# BBB_CNC_V3.net
KiCad netlist of a schematic drawn in EAGLE
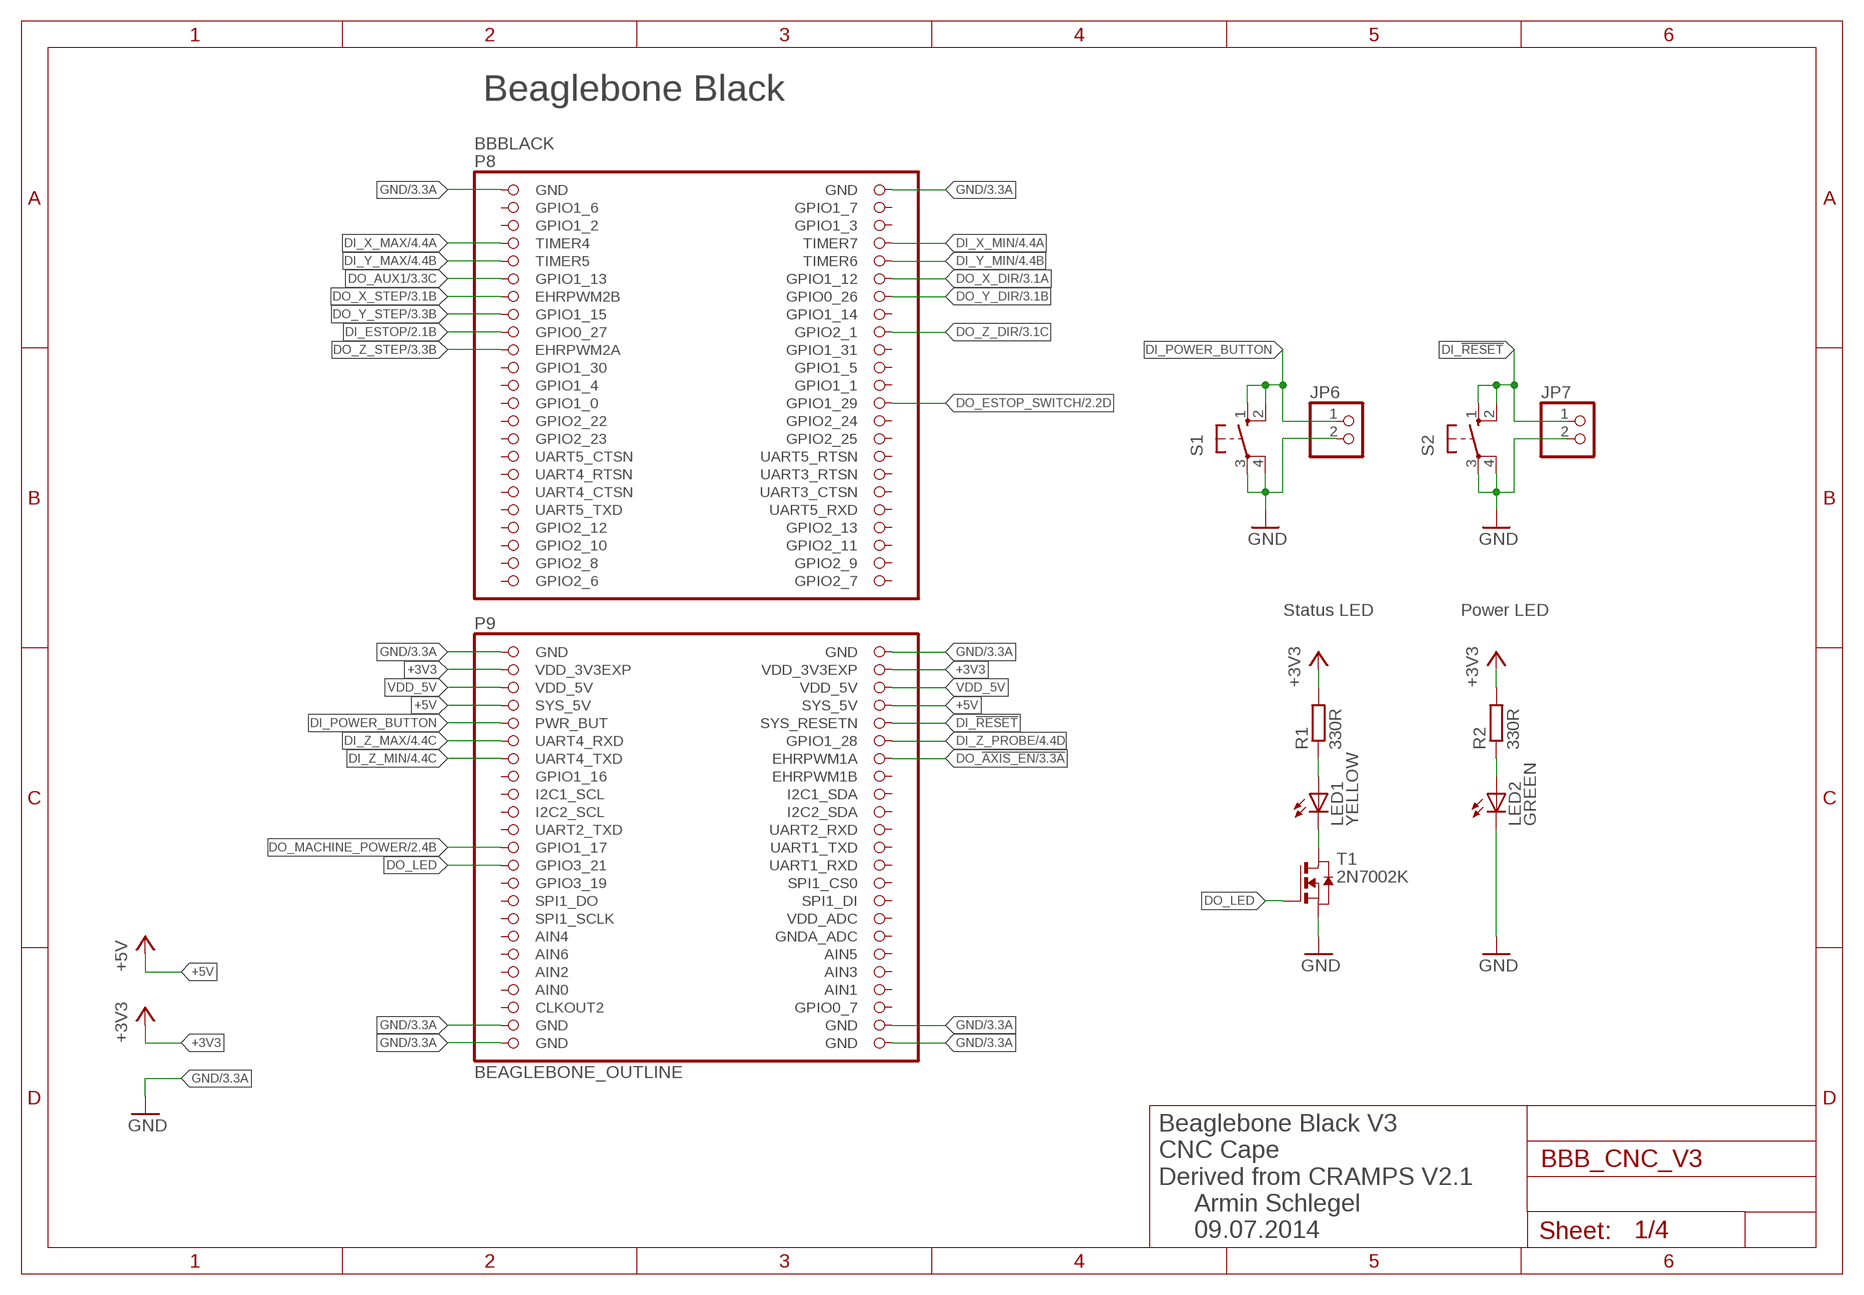
[diagram p0: schematic, sheet 1]
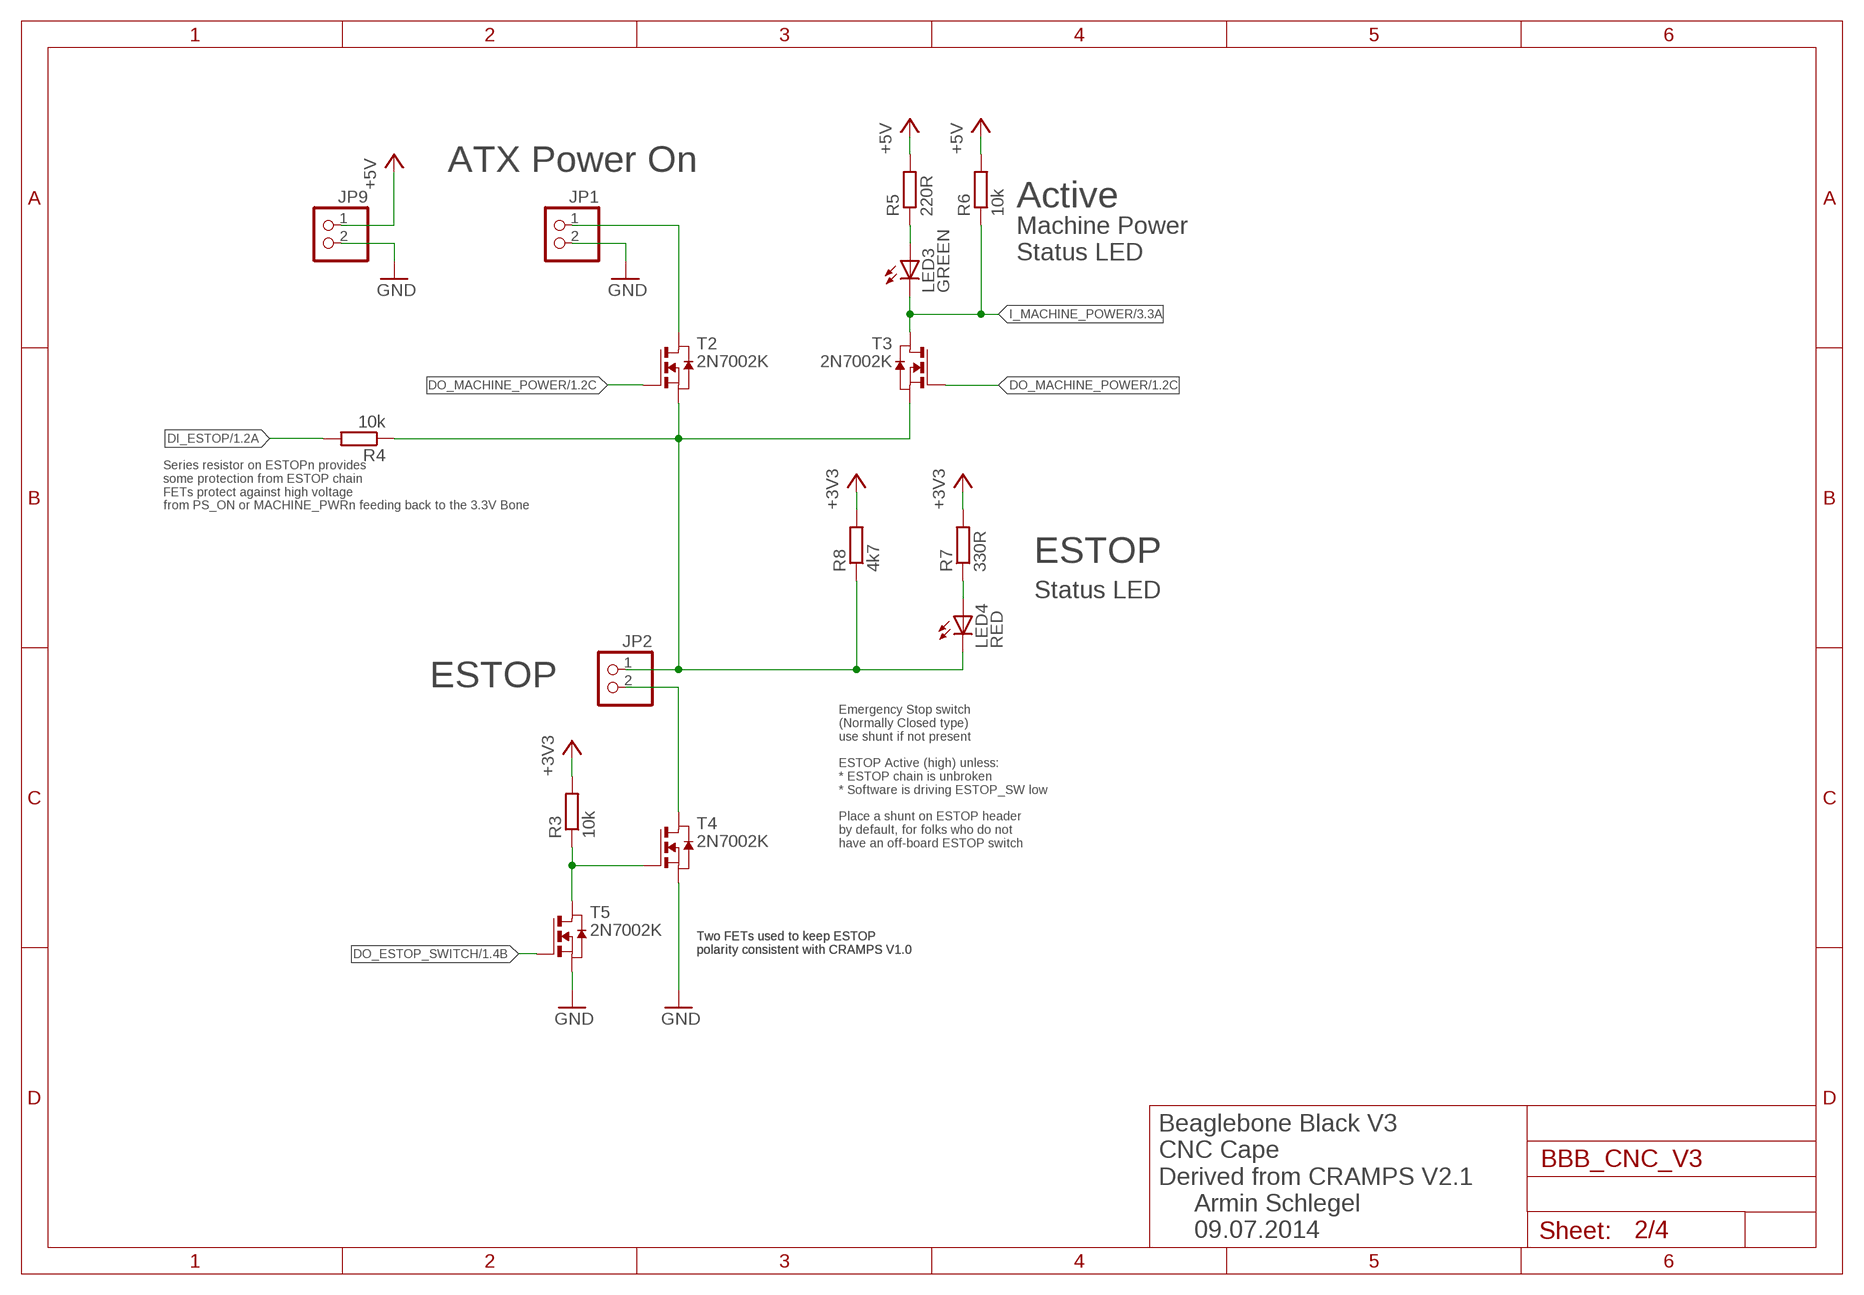
[diagram p1: schematic, sheet 2]
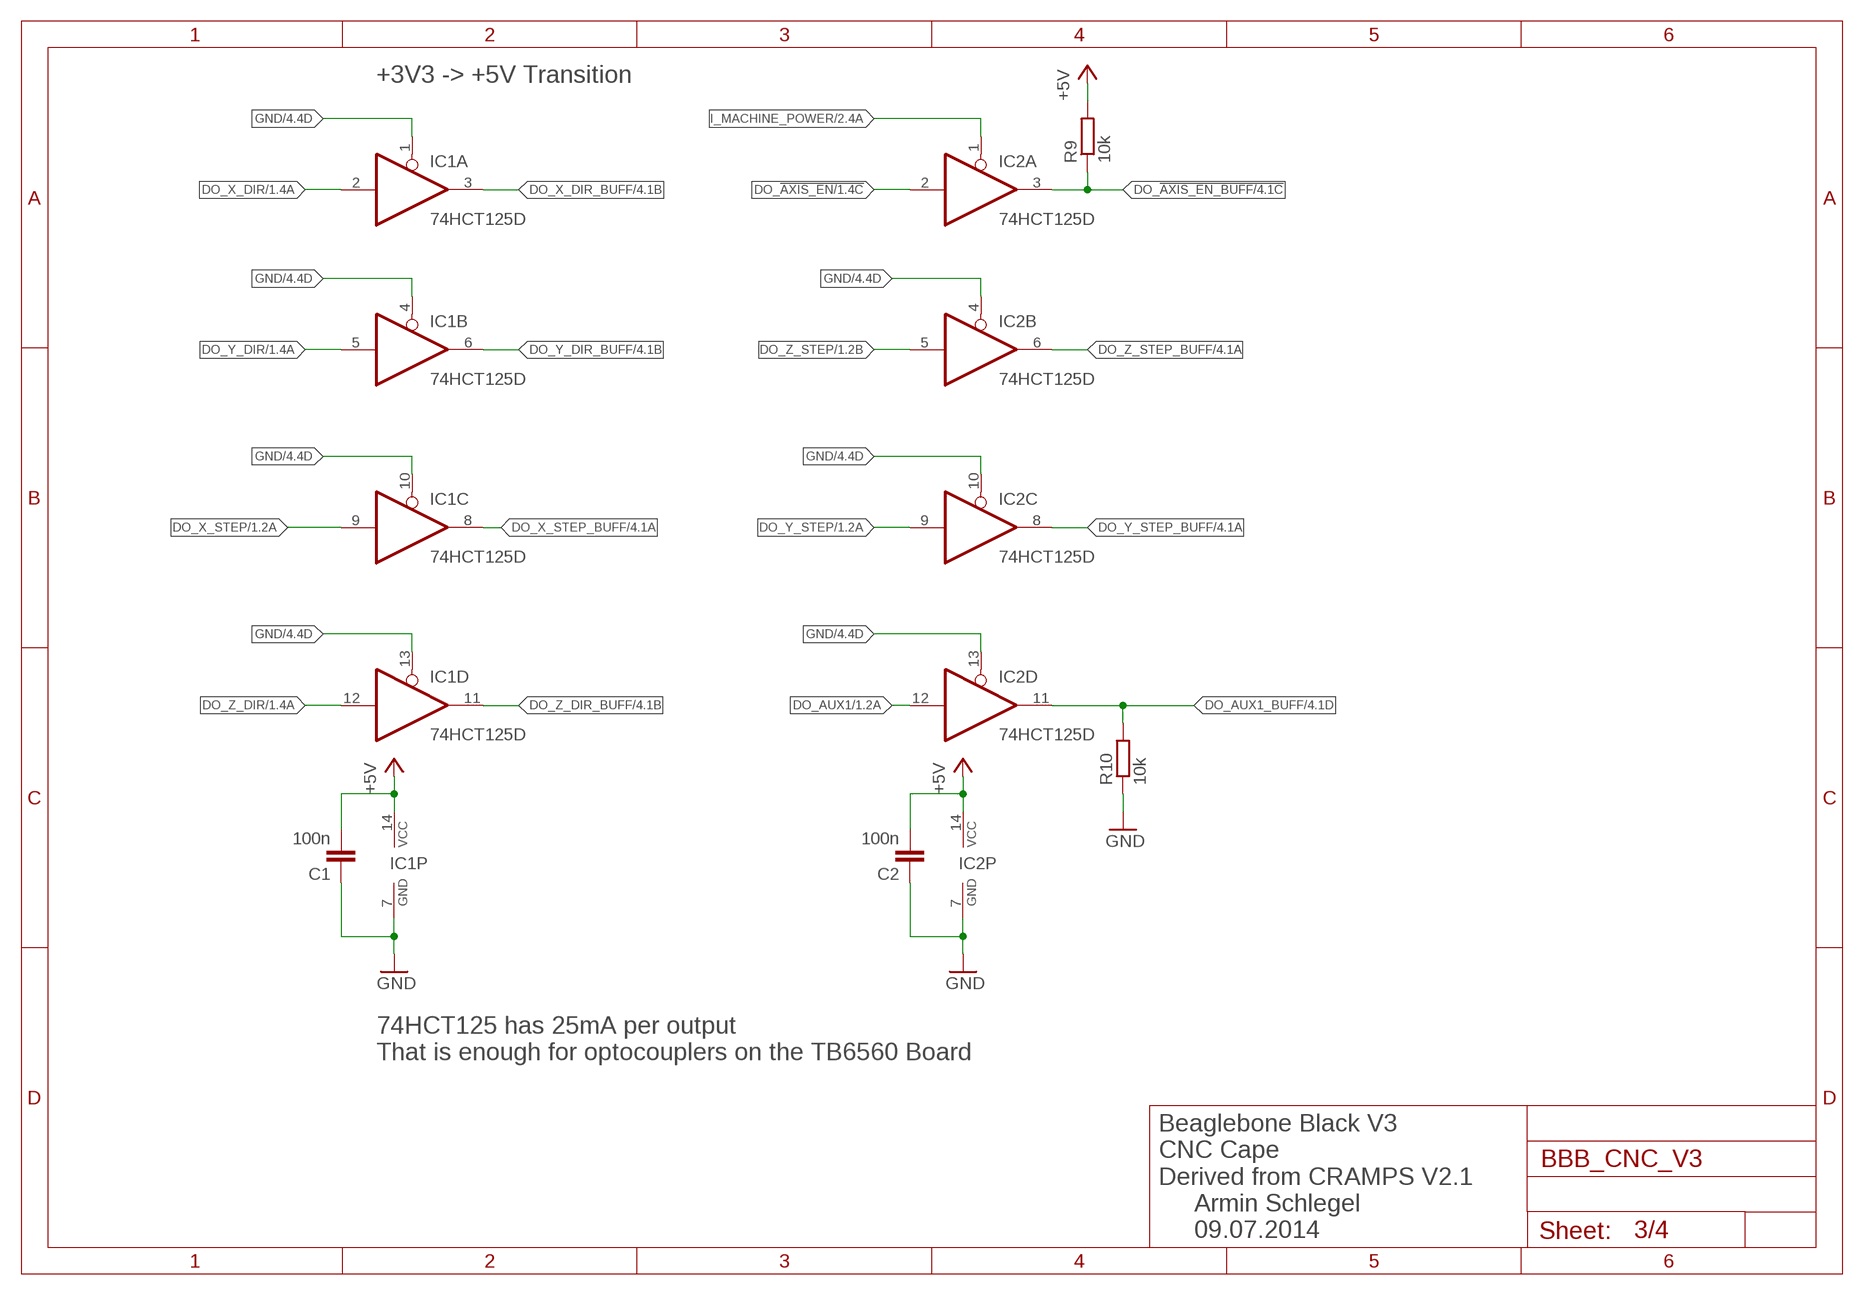
[diagram p2: schematic, sheet 3]
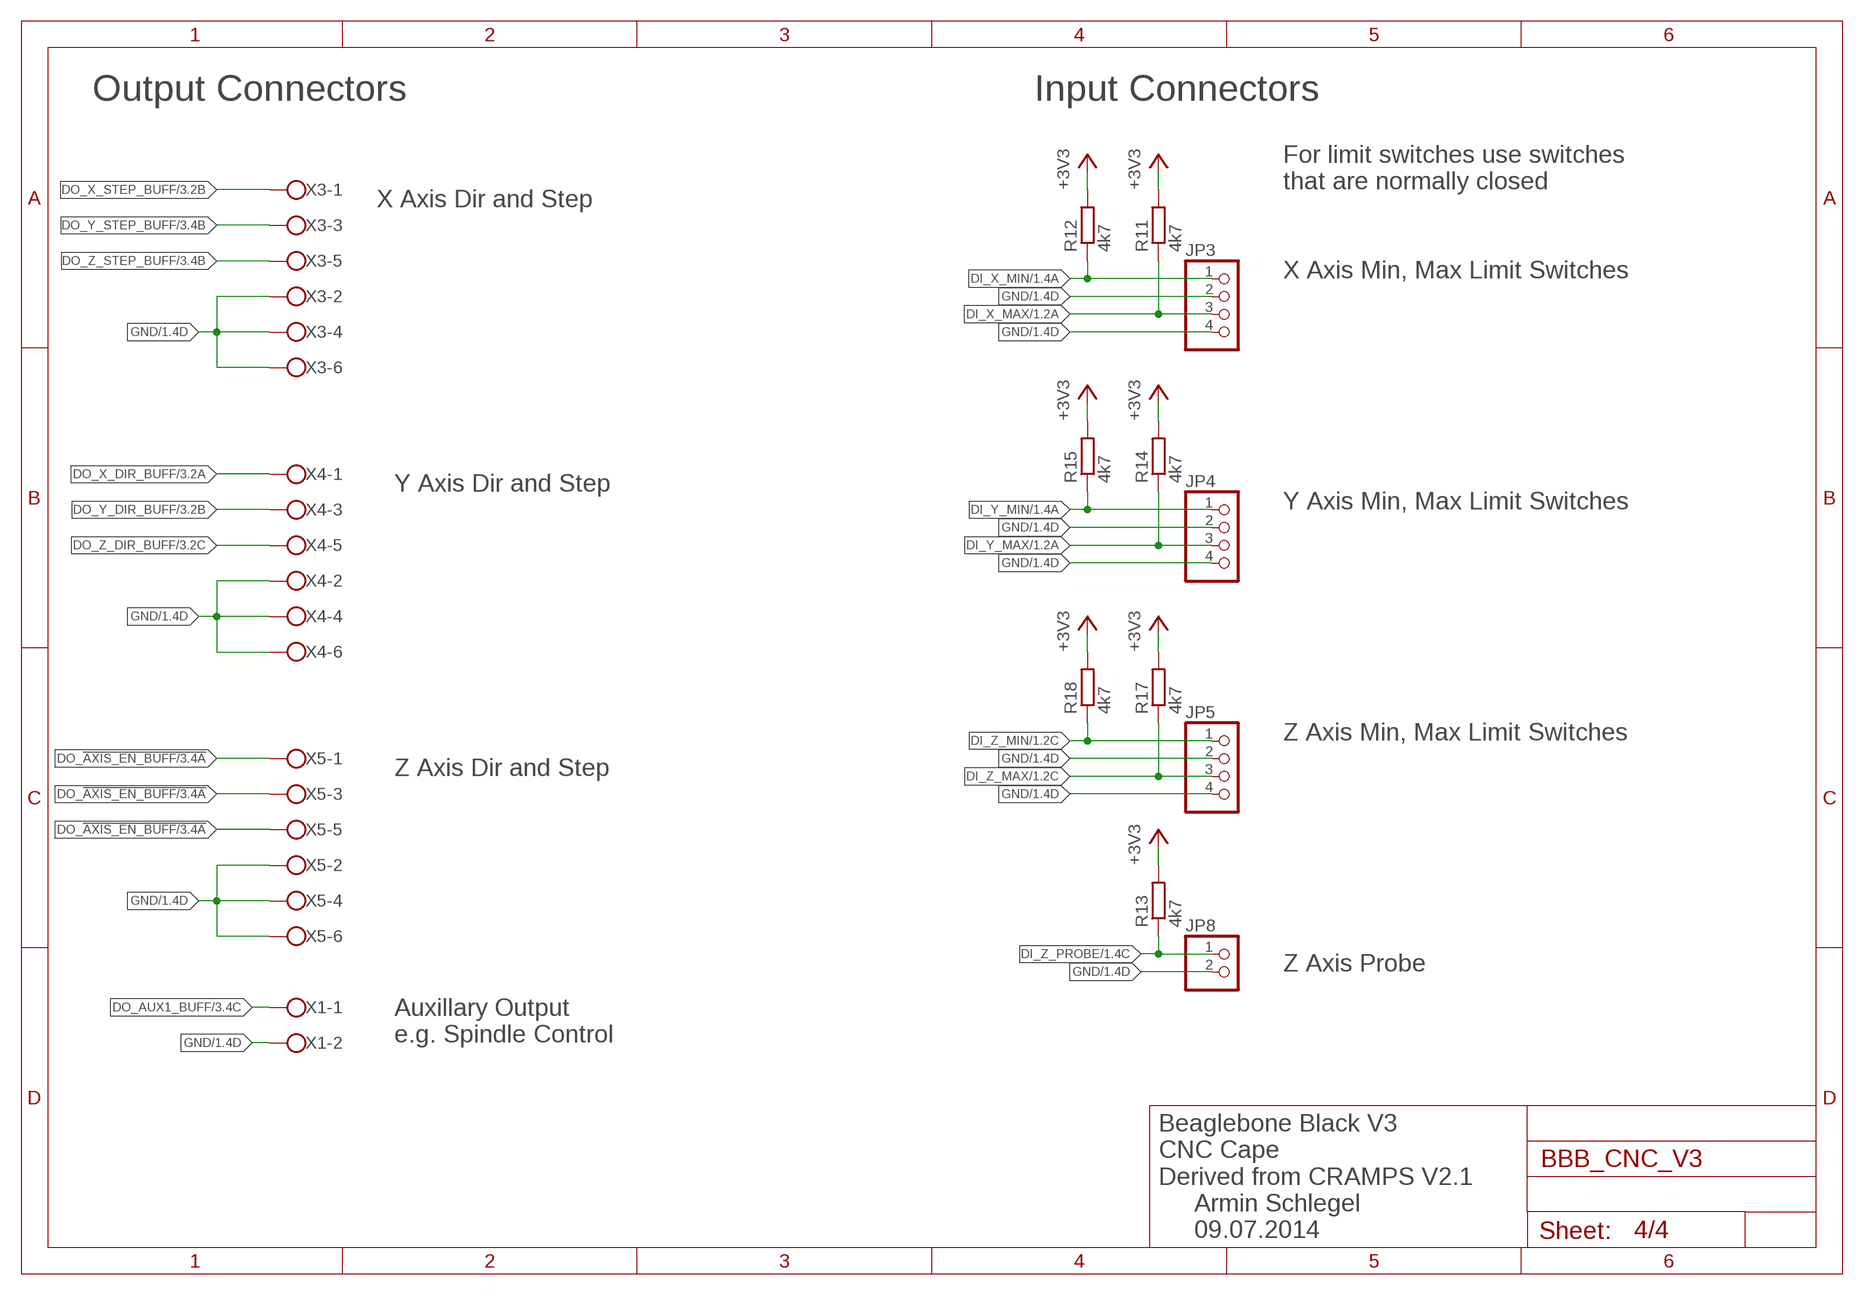
[diagram p3: schematic, sheet 4]

(export (version "E")
  (design (tool "Eeschema 10.0.6"))
  (components
    (comp (ref "BBBLACK")
      (value "BEAGLEBONE_OUTLINE")
      (footprint "eagle-import:BEAGLEBONE_SHIELD")
      (libsource (lib "eagle-import") (part "BEAGLEBONE_OUTLINE"))
    )
    (comp (ref "JP6")
      (value "PINHD-1X2")
      (footprint "eagle-import:1X02")
      (libsource (lib "eagle-import") (part "PINHD-1X2"))
    )
    (comp (ref "JP7")
      (value "PINHD-1X2")
      (footprint "eagle-import:1X02")
      (libsource (lib "eagle-import") (part "PINHD-1X2"))
    )
    (comp (ref "LED1")
      (value "YELLOW")
      (footprint "eagle-import:SML0805")
      (libsource (lib "eagle-import") (part "LEDSML0805"))
    )
    (comp (ref "LED2")
      (value "GREEN")
      (footprint "eagle-import:SML0805")
      (libsource (lib "eagle-import") (part "LEDSML0805"))
    )
    (comp (ref "R1")
      (value "330R")
      (footprint "eagle-import:R0603")
      (libsource (lib "eagle-import") (part "R-EU_R0603"))
    )
    (comp (ref "R2")
      (value "330R")
      (footprint "eagle-import:R0603")
      (libsource (lib "eagle-import") (part "R-EU_R0603"))
    )
    (comp (ref "S1")
      (value "10-XX")
      (footprint "eagle-import:B3F-10XX")
      (fields (field (name "MPN") "B3F-1000"))
      (libsource (lib "eagle-import") (part "10-XX"))
    )
    (comp (ref "S2")
      (value "10-XX")
      (footprint "eagle-import:B3F-10XX")
      (fields (field (name "MPN") "B3F-1000"))
      (libsource (lib "eagle-import") (part "10-XX"))
    )
    (comp (ref "T1")
      (value "2N7002K")
      (footprint "eagle-import:SOT-23")
      (libsource (lib "eagle-import") (part "NMOSSOT23"))
    )
    (comp (ref "JP1")
      (value "PINHD-1X2")
      (footprint "eagle-import:1X02")
      (libsource (lib "eagle-import") (part "PINHD-1X2"))
    )
    (comp (ref "JP2")
      (value "PINHD-1X2")
      (footprint "eagle-import:1X02")
      (libsource (lib "eagle-import") (part "PINHD-1X2"))
    )
    (comp (ref "JP9")
      (value "PINHD-1X2")
      (footprint "eagle-import:1X02")
      (libsource (lib "eagle-import") (part "PINHD-1X2"))
    )
    (comp (ref "LED3")
      (value "GREEN")
      (footprint "eagle-import:SML0805")
      (libsource (lib "eagle-import") (part "LEDSML0805"))
    )
    (comp (ref "LED4")
      (value "RED")
      (footprint "eagle-import:SML0805")
      (libsource (lib "eagle-import") (part "LEDSML0805"))
    )
    (comp (ref "R3")
      (value "10k")
      (footprint "eagle-import:R0603")
      (libsource (lib "eagle-import") (part "R-EU_R0603"))
    )
    (comp (ref "R4")
      (value "10k")
      (footprint "eagle-import:R0603")
      (libsource (lib "eagle-import") (part "R-EU_R0603"))
    )
    (comp (ref "R5")
      (value "220R")
      (footprint "eagle-import:R0603")
      (libsource (lib "eagle-import") (part "R-EU_R0603"))
    )
    (comp (ref "R6")
      (value "10k")
      (footprint "eagle-import:R0603")
      (libsource (lib "eagle-import") (part "R-EU_R0603"))
    )
    (comp (ref "R7")
      (value "330R")
      (footprint "eagle-import:R0603")
      (libsource (lib "eagle-import") (part "R-EU_R0603"))
    )
    (comp (ref "R8")
      (value "4k7")
      (footprint "eagle-import:R0603")
      (libsource (lib "eagle-import") (part "R-EU_R0603"))
    )
    (comp (ref "T2")
      (value "2N7002K")
      (footprint "eagle-import:SOT-23")
      (libsource (lib "eagle-import") (part "NMOSSOT23"))
    )
    (comp (ref "T3")
      (value "2N7002K")
      (footprint "eagle-import:SOT-23")
      (libsource (lib "eagle-import") (part "NMOSSOT23"))
    )
    (comp (ref "T4")
      (value "2N7002K")
      (footprint "eagle-import:SOT-23")
      (libsource (lib "eagle-import") (part "NMOSSOT23"))
    )
    (comp (ref "T5")
      (value "2N7002K")
      (footprint "eagle-import:SOT-23")
      (libsource (lib "eagle-import") (part "NMOSSOT23"))
    )
    (comp (ref "C1")
      (value "100n")
      (footprint "eagle-import:C0603K")
      (libsource (lib "eagle-import") (part "C-EUC0603K"))
    )
    (comp (ref "C2")
      (value "100n")
      (footprint "eagle-import:C0603K")
      (libsource (lib "eagle-import") (part "C-EUC0603K"))
    )
    (comp (ref "IC1")
      (value "74HCT125D")
      (footprint "eagle-import:SO14")
      (libsource (lib "eagle-import") (part "74125DHCT"))
    )
    (comp (ref "IC2")
      (value "74HCT125D")
      (footprint "eagle-import:SO14")
      (libsource (lib "eagle-import") (part "74125DHCT"))
    )
    (comp (ref "R9")
      (value "10k")
      (footprint "eagle-import:R0603")
      (libsource (lib "eagle-import") (part "R-EU_R0603"))
    )
    (comp (ref "R10")
      (value "10k")
      (footprint "eagle-import:R0603")
      (libsource (lib "eagle-import") (part "R-EU_R0603"))
    )
    (comp (ref "JP3")
      (value "PINHD-1X4")
      (footprint "eagle-import:1X04")
      (libsource (lib "eagle-import") (part "PINHD-1X4"))
    )
    (comp (ref "JP4")
      (value "PINHD-1X4")
      (footprint "eagle-import:1X04")
      (libsource (lib "eagle-import") (part "PINHD-1X4"))
    )
    (comp (ref "JP5")
      (value "PINHD-1X4")
      (footprint "eagle-import:1X04")
      (libsource (lib "eagle-import") (part "PINHD-1X4"))
    )
    (comp (ref "JP8")
      (value "PINHD-1X2")
      (footprint "eagle-import:1X02")
      (libsource (lib "eagle-import") (part "PINHD-1X2"))
    )
    (comp (ref "R11")
      (value "4k7")
      (footprint "eagle-import:R0603")
      (libsource (lib "eagle-import") (part "R-EU_R0603"))
    )
    (comp (ref "R12")
      (value "4k7")
      (footprint "eagle-import:R0603")
      (libsource (lib "eagle-import") (part "R-EU_R0603"))
    )
    (comp (ref "R13")
      (value "4k7")
      (footprint "eagle-import:R0603")
      (libsource (lib "eagle-import") (part "R-EU_R0603"))
    )
    (comp (ref "R14")
      (value "4k7")
      (footprint "eagle-import:R0603")
      (libsource (lib "eagle-import") (part "R-EU_R0603"))
    )
    (comp (ref "R15")
      (value "4k7")
      (footprint "eagle-import:R0603")
      (libsource (lib "eagle-import") (part "R-EU_R0603"))
    )
    (comp (ref "R17")
      (value "4k7")
      (footprint "eagle-import:R0603")
      (libsource (lib "eagle-import") (part "R-EU_R0603"))
    )
    (comp (ref "R18")
      (value "4k7")
      (footprint "eagle-import:R0603")
      (libsource (lib "eagle-import") (part "R-EU_R0603"))
    )
    (comp (ref "X1")
      (value "W237-102")
      (footprint "eagle-import:W237-102")
      (fields (field (name "MPN") "237-102"))
      (libsource (lib "eagle-import") (part "W237-102"))
    )
    (comp (ref "X3")
      (value "W237-136")
      (footprint "eagle-import:W237-136")
      (fields (field (name "MPN") "237-136"))
      (libsource (lib "eagle-import") (part "W237-136"))
    )
    (comp (ref "X4")
      (value "W237-136")
      (footprint "eagle-import:W237-136")
      (fields (field (name "MPN") "237-136"))
      (libsource (lib "eagle-import") (part "W237-136"))
    )
    (comp (ref "X5")
      (value "W237-136")
      (footprint "eagle-import:W237-136")
      (fields (field (name "MPN") "237-136"))
      (libsource (lib "eagle-import") (part "W237-136"))
    )
  )
  (nets
    (net (code "1") (name "+3V3") (class "Default")
      (node (ref "BBBLACK") (pin "49") (pinfunction "VDD_3V3EXP_49") (pintype "power_in"))
      (node (ref "BBBLACK") (pin "50") (pinfunction "VDD_3V3EXP_50") (pintype "power_in"))
      (node (ref "R1") (pin "2") (pinfunction "2_2") (pintype "passive"))
      (node (ref "R11") (pin "2") (pinfunction "2_2") (pintype "passive"))
      (node (ref "R12") (pin "2") (pinfunction "2_2") (pintype "passive"))
      (node (ref "R13") (pin "2") (pinfunction "2_2") (pintype "passive"))
      (node (ref "R14") (pin "2") (pinfunction "2_2") (pintype "passive"))
      (node (ref "R15") (pin "2") (pinfunction "2_2") (pintype "passive"))
      (node (ref "R17") (pin "2") (pinfunction "2_2") (pintype "passive"))
      (node (ref "R18") (pin "2") (pinfunction "2_2") (pintype "passive"))
      (node (ref "R2") (pin "2") (pinfunction "2_2") (pintype "passive"))
      (node (ref "R3") (pin "2") (pinfunction "2_2") (pintype "passive"))
      (node (ref "R7") (pin "2") (pinfunction "2_2") (pintype "passive"))
      (node (ref "R8") (pin "2") (pinfunction "2_2") (pintype "passive"))
    )
    (net (code "2") (name "+5V") (class "Default")
      (node (ref "BBBLACK") (pin "53") (pinfunction "SYS_5V_53") (pintype "power_in"))
      (node (ref "BBBLACK") (pin "54") (pinfunction "SYS_5V_54") (pintype "passive"))
      (node (ref "C1") (pin "2") (pinfunction "2_2") (pintype "passive"))
      (node (ref "C2") (pin "2") (pinfunction "2_2") (pintype "passive"))
      (node (ref "IC1") (pin "14") (pinfunction "VCC_14") (pintype "power_in"))
      (node (ref "IC2") (pin "14") (pinfunction "VCC_14") (pintype "power_in"))
      (node (ref "JP9") (pin "1") (pinfunction "1_1") (pintype "passive"))
      (node (ref "R5") (pin "2") (pinfunction "2_2") (pintype "passive"))
      (node (ref "R6") (pin "2") (pinfunction "2_2") (pintype "passive"))
      (node (ref "R9") (pin "2") (pinfunction "2_2") (pintype "passive"))
    )
    (net (code "3") (name "AIN0") (class "Default")
      (node (ref "BBBLACK") (pin "85") (pinfunction "AIN0_85") (pintype "power_in"))
    )
    (net (code "4") (name "DI_ESTOP") (class "Default")
      (node (ref "BBBLACK") (pin "17") (pinfunction "GPIO0_27_17") (pintype "passive"))
      (node (ref "R4") (pin "2") (pinfunction "2_2") (pintype "passive"))
    )
    (net (code "5") (name "DI_POWER_BUTTON") (class "Default")
      (node (ref "BBBLACK") (pin "55") (pinfunction "PWR_BUT_55") (pintype "passive"))
      (node (ref "JP6") (pin "1") (pinfunction "1_1") (pintype "passive"))
      (node (ref "S1") (pin "1") (pinfunction "S_1") (pintype "passive"))
      (node (ref "S1") (pin "2") (pinfunction "S1_2") (pintype "passive"))
    )
    (net (code "6") (name "DI_X_MAX") (class "Default")
      (node (ref "BBBLACK") (pin "7") (pinfunction "TIMER4_7") (pintype "passive"))
      (node (ref "JP3") (pin "3") (pinfunction "3_3") (pintype "passive"))
      (node (ref "R11") (pin "1") (pinfunction "1_1") (pintype "passive"))
    )
    (net (code "7") (name "DI_X_MIN") (class "Default")
      (node (ref "BBBLACK") (pin "8") (pinfunction "TIMER7_8") (pintype "passive"))
      (node (ref "JP3") (pin "1") (pinfunction "1_1") (pintype "passive"))
      (node (ref "R12") (pin "1") (pinfunction "1_1") (pintype "passive"))
    )
    (net (code "8") (name "DI_Y_MAX") (class "Default")
      (node (ref "BBBLACK") (pin "9") (pinfunction "TIMER5_9") (pintype "passive"))
      (node (ref "JP4") (pin "3") (pinfunction "3_3") (pintype "passive"))
      (node (ref "R14") (pin "1") (pinfunction "1_1") (pintype "passive"))
    )
    (net (code "9") (name "DI_Y_MIN") (class "Default")
      (node (ref "BBBLACK") (pin "10") (pinfunction "TIMER6_10") (pintype "passive"))
      (node (ref "JP4") (pin "1") (pinfunction "1_1") (pintype "passive"))
      (node (ref "R15") (pin "1") (pinfunction "1_1") (pintype "passive"))
    )
    (net (code "10") (name "DI_Z_MAX") (class "Default")
      (node (ref "BBBLACK") (pin "57") (pinfunction "UART4_RXD_57") (pintype "passive"))
      (node (ref "JP5") (pin "3") (pinfunction "3_3") (pintype "passive"))
      (node (ref "R17") (pin "1") (pinfunction "1_1") (pintype "passive"))
    )
    (net (code "11") (name "DI_Z_MIN") (class "Default")
      (node (ref "BBBLACK") (pin "59") (pinfunction "UART4_TXD_59") (pintype "passive"))
      (node (ref "JP5") (pin "1") (pinfunction "1_1") (pintype "passive"))
      (node (ref "R18") (pin "1") (pinfunction "1_1") (pintype "passive"))
    )
    (net (code "12") (name "DI_Z_PROBE") (class "Default")
      (node (ref "BBBLACK") (pin "58") (pinfunction "GPIO1_28_58") (pintype "passive"))
      (node (ref "JP8") (pin "1") (pinfunction "1_1") (pintype "passive"))
      (node (ref "R13") (pin "1") (pinfunction "1_1") (pintype "passive"))
    )
    (net (code "13") (name "DI_~{RESET}") (class "Default")
      (node (ref "BBBLACK") (pin "56") (pinfunction "SYS_RESETN_56") (pintype "passive"))
      (node (ref "JP7") (pin "1") (pinfunction "1_1") (pintype "passive"))
      (node (ref "S2") (pin "1") (pinfunction "S_1") (pintype "passive"))
      (node (ref "S2") (pin "2") (pinfunction "S1_2") (pintype "passive"))
    )
    (net (code "14") (name "DO_AUX1") (class "Default")
      (node (ref "BBBLACK") (pin "11") (pinfunction "GPIO1_13_11") (pintype "passive"))
      (node (ref "IC2") (pin "12") (pinfunction "I_12") (pintype "input"))
    )
    (net (code "15") (name "DO_AUX1_BUFF") (class "Default")
      (node (ref "IC2") (pin "11") (pinfunction "O_11") (pintype "tri_state"))
      (node (ref "R10") (pin "2") (pinfunction "2_2") (pintype "passive"))
      (node (ref "X1") (pin "1") (pinfunction "KL_1") (pintype "passive"))
    )
    (net (code "16") (name "DO_ESTOP_SWITCH") (class "Default")
      (node (ref "BBBLACK") (pin "26") (pinfunction "GPIO1_29_26") (pintype "passive"))
      (node (ref "T5") (pin "3") (pinfunction "G_3") (pintype "passive"))
    )
    (net (code "17") (name "DO_LED") (class "Default")
      (node (ref "BBBLACK") (pin "71") (pinfunction "GPIO3_21_71") (pintype "passive"))
      (node (ref "T1") (pin "3") (pinfunction "G_3") (pintype "passive"))
    )
    (net (code "18") (name "DO_MACHINE_POWER") (class "Default")
      (node (ref "BBBLACK") (pin "69") (pinfunction "GPIO1_17_69") (pintype "passive"))
      (node (ref "T2") (pin "3") (pinfunction "G_3") (pintype "passive"))
      (node (ref "T3") (pin "3") (pinfunction "G_3") (pintype "passive"))
    )
    (net (code "19") (name "DO_X_DIR") (class "Default")
      (node (ref "BBBLACK") (pin "12") (pinfunction "GPIO1_12_12") (pintype "passive"))
      (node (ref "IC1") (pin "2") (pinfunction "I_2") (pintype "input"))
    )
    (net (code "20") (name "DO_X_DIR_BUFF") (class "Default")
      (node (ref "IC1") (pin "3") (pinfunction "O_3") (pintype "tri_state"))
      (node (ref "X4") (pin "1") (pinfunction "KL_1") (pintype "passive"))
    )
    (net (code "21") (name "DO_X_STEP") (class "Default")
      (node (ref "BBBLACK") (pin "13") (pinfunction "EHRPWM2B_13") (pintype "passive"))
      (node (ref "IC1") (pin "9") (pinfunction "I_9") (pintype "input"))
    )
    (net (code "22") (name "DO_X_STEP_BUFF") (class "Default")
      (node (ref "IC1") (pin "8") (pinfunction "O_8") (pintype "tri_state"))
      (node (ref "X3") (pin "1") (pinfunction "KL_1") (pintype "passive"))
    )
    (net (code "23") (name "DO_Y_DIR") (class "Default")
      (node (ref "BBBLACK") (pin "14") (pinfunction "GPIO0_26_14") (pintype "passive"))
      (node (ref "IC1") (pin "5") (pinfunction "I_5") (pintype "input"))
    )
    (net (code "24") (name "DO_Y_DIR_BUFF") (class "Default")
      (node (ref "IC1") (pin "6") (pinfunction "O_6") (pintype "tri_state"))
      (node (ref "X4") (pin "3") (pinfunction "KL_3") (pintype "passive"))
    )
    (net (code "25") (name "DO_Y_STEP") (class "Default")
      (node (ref "BBBLACK") (pin "15") (pinfunction "GPIO1_15_15") (pintype "passive"))
      (node (ref "IC2") (pin "9") (pinfunction "I_9") (pintype "input"))
    )
    (net (code "26") (name "DO_Y_STEP_BUFF") (class "Default")
      (node (ref "IC2") (pin "8") (pinfunction "O_8") (pintype "tri_state"))
      (node (ref "X3") (pin "3") (pinfunction "KL_3") (pintype "passive"))
    )
    (net (code "27") (name "DO_Z_DIR") (class "Default")
      (node (ref "BBBLACK") (pin "18") (pinfunction "GPIO2_1_18") (pintype "passive"))
      (node (ref "IC1") (pin "12") (pinfunction "I_12") (pintype "input"))
    )
    (net (code "28") (name "DO_Z_DIR_BUFF") (class "Default")
      (node (ref "IC1") (pin "11") (pinfunction "O_11") (pintype "tri_state"))
      (node (ref "X4") (pin "5") (pinfunction "KL_5") (pintype "passive"))
    )
    (net (code "29") (name "DO_Z_STEP") (class "Default")
      (node (ref "BBBLACK") (pin "19") (pinfunction "EHRPWM2A_19") (pintype "passive"))
      (node (ref "IC2") (pin "5") (pinfunction "I_5") (pintype "input"))
    )
    (net (code "30") (name "DO_Z_STEP_BUFF") (class "Default")
      (node (ref "IC2") (pin "6") (pinfunction "O_6") (pintype "tri_state"))
      (node (ref "X3") (pin "5") (pinfunction "KL_5") (pintype "passive"))
    )
    (net (code "31") (name "DO_~{AXIS_EN_BUFF}") (class "Default")
      (node (ref "IC2") (pin "3") (pinfunction "O_3") (pintype "tri_state"))
      (node (ref "R9") (pin "1") (pinfunction "1_1") (pintype "passive"))
      (node (ref "X5") (pin "1") (pinfunction "KL_1") (pintype "passive"))
      (node (ref "X5") (pin "3") (pinfunction "KL_3") (pintype "passive"))
      (node (ref "X5") (pin "5") (pinfunction "KL_5") (pintype "passive"))
    )
    (net (code "32") (name "DO_~{AXIS_EN}") (class "Default")
      (node (ref "BBBLACK") (pin "60") (pinfunction "EHRPWM1A_60") (pintype "passive"))
      (node (ref "IC2") (pin "2") (pinfunction "I_2") (pintype "input"))
    )
    (net (code "33") (name "GND") (class "Default")
      (node (ref "BBBLACK") (pin "1") (pinfunction "GND_1") (pintype "power_in"))
      (node (ref "BBBLACK") (pin "2") (pinfunction "GND_2") (pintype "power_in"))
      (node (ref "BBBLACK") (pin "47") (pinfunction "GND_47") (pintype "power_in"))
      (node (ref "BBBLACK") (pin "48") (pinfunction "GND_48") (pintype "power_in"))
      (node (ref "BBBLACK") (pin "89") (pinfunction "GND_89") (pintype "power_in"))
      (node (ref "BBBLACK") (pin "90") (pinfunction "GND_90") (pintype "power_in"))
      (node (ref "BBBLACK") (pin "91") (pinfunction "GND_91") (pintype "power_in"))
      (node (ref "BBBLACK") (pin "92") (pinfunction "GND_92") (pintype "power_in"))
      (node (ref "C1") (pin "1") (pinfunction "1_1") (pintype "passive"))
      (node (ref "C2") (pin "1") (pinfunction "1_1") (pintype "passive"))
      (node (ref "IC1") (pin "1") (pinfunction "OE_1") (pintype "input"))
      (node (ref "IC1") (pin "10") (pinfunction "OE_10") (pintype "input"))
      (node (ref "IC1") (pin "13") (pinfunction "OE_13") (pintype "input"))
      (node (ref "IC1") (pin "4") (pinfunction "OE_4") (pintype "input"))
      (node (ref "IC1") (pin "7") (pinfunction "GND_7") (pintype "power_in"))
      (node (ref "IC2") (pin "10") (pinfunction "OE_10") (pintype "input"))
      (node (ref "IC2") (pin "13") (pinfunction "OE_13") (pintype "input"))
      (node (ref "IC2") (pin "4") (pinfunction "OE_4") (pintype "input"))
      (node (ref "IC2") (pin "7") (pinfunction "GND_7") (pintype "power_in"))
      (node (ref "JP1") (pin "2") (pinfunction "2_2") (pintype "passive"))
      (node (ref "JP3") (pin "2") (pinfunction "2_2") (pintype "passive"))
      (node (ref "JP3") (pin "4") (pinfunction "4_4") (pintype "passive"))
      (node (ref "JP4") (pin "2") (pinfunction "2_2") (pintype "passive"))
      (node (ref "JP4") (pin "4") (pinfunction "4_4") (pintype "passive"))
      (node (ref "JP5") (pin "2") (pinfunction "2_2") (pintype "passive"))
      (node (ref "JP5") (pin "4") (pinfunction "4_4") (pintype "passive"))
      (node (ref "JP6") (pin "2") (pinfunction "2_2") (pintype "passive"))
      (node (ref "JP7") (pin "2") (pinfunction "2_2") (pintype "passive"))
      (node (ref "JP8") (pin "2") (pinfunction "2_2") (pintype "passive"))
      (node (ref "JP9") (pin "2") (pinfunction "2_2") (pintype "passive"))
      (node (ref "LED2") (pin "C") (pinfunction "C_C") (pintype "passive"))
      (node (ref "R10") (pin "1") (pinfunction "1_1") (pintype "passive"))
      (node (ref "S1") (pin "3") (pinfunction "P_3") (pintype "passive"))
      (node (ref "S1") (pin "4") (pinfunction "P1_4") (pintype "passive"))
      (node (ref "S2") (pin "3") (pinfunction "P_3") (pintype "passive"))
      (node (ref "S2") (pin "4") (pinfunction "P1_4") (pintype "passive"))
      (node (ref "T1") (pin "2") (pinfunction "S_2") (pintype "passive"))
      (node (ref "T4") (pin "2") (pinfunction "S_2") (pintype "passive"))
      (node (ref "T5") (pin "2") (pinfunction "S_2") (pintype "passive"))
      (node (ref "X1") (pin "2") (pinfunction "KL_2") (pintype "passive"))
      (node (ref "X3") (pin "2") (pinfunction "KL_2") (pintype "passive"))
      (node (ref "X3") (pin "4") (pinfunction "KL_4") (pintype "passive"))
      (node (ref "X3") (pin "6") (pinfunction "KL_6") (pintype "passive"))
      (node (ref "X4") (pin "2") (pinfunction "KL_2") (pintype "passive"))
      (node (ref "X4") (pin "4") (pinfunction "KL_4") (pintype "passive"))
      (node (ref "X4") (pin "6") (pinfunction "KL_6") (pintype "passive"))
      (node (ref "X5") (pin "2") (pinfunction "KL_2") (pintype "passive"))
      (node (ref "X5") (pin "4") (pinfunction "KL_4") (pintype "passive"))
      (node (ref "X5") (pin "6") (pinfunction "KL_6") (pintype "passive"))
    )
    (net (code "34") (name "I_MACHINE_POWER") (class "Default")
      (node (ref "IC2") (pin "1") (pinfunction "OE_1") (pintype "input"))
      (node (ref "LED3") (pin "C") (pinfunction "C_C") (pintype "passive"))
      (node (ref "R6") (pin "1") (pinfunction "1_1") (pintype "passive"))
      (node (ref "T3") (pin "1") (pinfunction "D_1") (pintype "passive"))
    )
    (net (code "35") (name "Net-(LED1-PadA)") (class "Default")
      (node (ref "LED1") (pin "A") (pinfunction "A_A") (pintype "passive"))
      (node (ref "R1") (pin "1") (pinfunction "1_1") (pintype "passive"))
    )
    (net (code "36") (name "Net-(LED2-PadA)") (class "Default")
      (node (ref "LED2") (pin "A") (pinfunction "A_A") (pintype "passive"))
      (node (ref "R2") (pin "1") (pinfunction "1_1") (pintype "passive"))
    )
    (net (code "37") (name "Net-(LED3-PadA)") (class "Default")
      (node (ref "LED3") (pin "A") (pinfunction "A_A") (pintype "passive"))
      (node (ref "R5") (pin "1") (pinfunction "1_1") (pintype "passive"))
    )
    (net (code "38") (name "Net-(LED4-PadA)") (class "Default")
      (node (ref "LED4") (pin "A") (pinfunction "A_A") (pintype "passive"))
      (node (ref "R7") (pin "1") (pinfunction "1_1") (pintype "passive"))
    )
    (net (code "39") (name "Net-(T1-D)") (class "Default")
      (node (ref "LED1") (pin "C") (pinfunction "C_C") (pintype "passive"))
      (node (ref "T1") (pin "1") (pinfunction "D_1") (pintype "passive"))
    )
    (net (code "40") (name "Net-(T2-D)") (class "Default")
      (node (ref "JP1") (pin "1") (pinfunction "1_1") (pintype "passive"))
      (node (ref "T2") (pin "1") (pinfunction "D_1") (pintype "passive"))
    )
    (net (code "41") (name "Net-(T2-S)") (class "Default")
      (node (ref "JP2") (pin "1") (pinfunction "1_1") (pintype "passive"))
      (node (ref "LED4") (pin "C") (pinfunction "C_C") (pintype "passive"))
      (node (ref "R4") (pin "1") (pinfunction "1_1") (pintype "passive"))
      (node (ref "R8") (pin "1") (pinfunction "1_1") (pintype "passive"))
      (node (ref "T2") (pin "2") (pinfunction "S_2") (pintype "passive"))
      (node (ref "T3") (pin "2") (pinfunction "S_2") (pintype "passive"))
    )
    (net (code "42") (name "Net-(T4-D)") (class "Default")
      (node (ref "JP2") (pin "2") (pinfunction "2_2") (pintype "passive"))
      (node (ref "T4") (pin "1") (pinfunction "D_1") (pintype "passive"))
    )
    (net (code "43") (name "Net-(T4-G)") (class "Default")
      (node (ref "R3") (pin "1") (pinfunction "1_1") (pintype "passive"))
      (node (ref "T4") (pin "3") (pinfunction "G_3") (pintype "passive"))
      (node (ref "T5") (pin "1") (pinfunction "D_1") (pintype "passive"))
    )
    (net (code "44") (name "VDD_5V") (class "Default")
      (node (ref "BBBLACK") (pin "51") (pinfunction "VDD_5V_51") (pintype "power_in"))
      (node (ref "BBBLACK") (pin "52") (pinfunction "VDD_5V_52") (pintype "power_in"))
    )
    (net (code "45") (name "unconnected-(BBBLACK-AIN1-Pad86)") (class "Default")
      (node (ref "BBBLACK") (pin "86") (pinfunction "AIN1_86") (pintype "passive"))
    )
    (net (code "46") (name "unconnected-(BBBLACK-AIN2-Pad83)") (class "Default")
      (node (ref "BBBLACK") (pin "83") (pinfunction "AIN2_83") (pintype "passive"))
    )
    (net (code "47") (name "unconnected-(BBBLACK-AIN3-Pad84)") (class "Default")
      (node (ref "BBBLACK") (pin "84") (pinfunction "AIN3_84") (pintype "passive"))
    )
    (net (code "48") (name "unconnected-(BBBLACK-AIN4-Pad79)") (class "Default")
      (node (ref "BBBLACK") (pin "79") (pinfunction "AIN4_79") (pintype "passive"))
    )
    (net (code "49") (name "unconnected-(BBBLACK-AIN5-Pad82)") (class "Default")
      (node (ref "BBBLACK") (pin "82") (pinfunction "AIN5_82") (pintype "passive"))
    )
    (net (code "50") (name "unconnected-(BBBLACK-AIN6-Pad81)") (class "Default")
      (node (ref "BBBLACK") (pin "81") (pinfunction "AIN6_81") (pintype "passive"))
    )
    (net (code "51") (name "unconnected-(BBBLACK-CLKOUT2-Pad87)") (class "Default")
      (node (ref "BBBLACK") (pin "87") (pinfunction "CLKOUT2_87") (pintype "input"))
    )
    (net (code "52") (name "unconnected-(BBBLACK-EHRPWM1B-Pad62)") (class "Default")
      (node (ref "BBBLACK") (pin "62") (pinfunction "EHRPWM1B_62") (pintype "passive"))
    )
    (net (code "53") (name "unconnected-(BBBLACK-GNDA_ADC-Pad80)") (class "Default")
      (node (ref "BBBLACK") (pin "80") (pinfunction "GNDA_ADC_80") (pintype "passive"))
    )
    (net (code "54") (name "unconnected-(BBBLACK-GPIO0_7-Pad88)") (class "Default")
      (node (ref "BBBLACK") (pin "88") (pinfunction "GPIO0_7_88") (pintype "passive"))
    )
    (net (code "55") (name "unconnected-(BBBLACK-GPIO1_0-Pad25)") (class "Default")
      (node (ref "BBBLACK") (pin "25") (pinfunction "GPIO1_0_25") (pintype "passive"))
    )
    (net (code "56") (name "unconnected-(BBBLACK-GPIO1_1-Pad24)") (class "Default")
      (node (ref "BBBLACK") (pin "24") (pinfunction "GPIO1_1_24") (pintype "passive"))
    )
    (net (code "57") (name "unconnected-(BBBLACK-GPIO1_2-Pad5)") (class "Default")
      (node (ref "BBBLACK") (pin "5") (pinfunction "GPIO1_2_5") (pintype "passive"))
    )
    (net (code "58") (name "unconnected-(BBBLACK-GPIO1_3-Pad6)") (class "Default")
      (node (ref "BBBLACK") (pin "6") (pinfunction "GPIO1_3_6") (pintype "passive"))
    )
    (net (code "59") (name "unconnected-(BBBLACK-GPIO1_4-Pad23)") (class "Default")
      (node (ref "BBBLACK") (pin "23") (pinfunction "GPIO1_4_23") (pintype "passive"))
    )
    (net (code "60") (name "unconnected-(BBBLACK-GPIO1_5-Pad22)") (class "Default")
      (node (ref "BBBLACK") (pin "22") (pinfunction "GPIO1_5_22") (pintype "passive"))
    )
    (net (code "61") (name "unconnected-(BBBLACK-GPIO1_6-Pad3)") (class "Default")
      (node (ref "BBBLACK") (pin "3") (pinfunction "GPIO1_6_3") (pintype "passive"))
    )
    (net (code "62") (name "unconnected-(BBBLACK-GPIO1_7-Pad4)") (class "Default")
      (node (ref "BBBLACK") (pin "4") (pinfunction "GPIO1_7_4") (pintype "passive"))
    )
    (net (code "63") (name "unconnected-(BBBLACK-GPIO1_14-Pad16)") (class "Default")
      (node (ref "BBBLACK") (pin "16") (pinfunction "GPIO1_14_16") (pintype "passive"))
    )
    (net (code "64") (name "unconnected-(BBBLACK-GPIO1_16-Pad61)") (class "Default")
      (node (ref "BBBLACK") (pin "61") (pinfunction "GPIO1_16_61") (pintype "passive"))
    )
    (net (code "65") (name "unconnected-(BBBLACK-GPIO1_30-Pad21)") (class "Default")
      (node (ref "BBBLACK") (pin "21") (pinfunction "GPIO1_30_21") (pintype "passive"))
    )
    (net (code "66") (name "unconnected-(BBBLACK-GPIO1_31-Pad20)") (class "Default")
      (node (ref "BBBLACK") (pin "20") (pinfunction "GPIO1_31_20") (pintype "passive"))
    )
    (net (code "67") (name "unconnected-(BBBLACK-GPIO2_6-Pad45)") (class "Default")
      (node (ref "BBBLACK") (pin "45") (pinfunction "GPIO2_6_45") (pintype "passive"))
    )
    (net (code "68") (name "unconnected-(BBBLACK-GPIO2_7-Pad46)") (class "Default")
      (node (ref "BBBLACK") (pin "46") (pinfunction "GPIO2_7_46") (pintype "passive"))
    )
    (net (code "69") (name "unconnected-(BBBLACK-GPIO2_8-Pad43)") (class "Default")
      (node (ref "BBBLACK") (pin "43") (pinfunction "GPIO2_8_43") (pintype "passive"))
    )
    (net (code "70") (name "unconnected-(BBBLACK-GPIO2_9-Pad44)") (class "Default")
      (node (ref "BBBLACK") (pin "44") (pinfunction "GPIO2_9_44") (pintype "passive"))
    )
    (net (code "71") (name "unconnected-(BBBLACK-GPIO2_10-Pad41)") (class "Default")
      (node (ref "BBBLACK") (pin "41") (pinfunction "GPIO2_10_41") (pintype "passive"))
    )
    (net (code "72") (name "unconnected-(BBBLACK-GPIO2_11-Pad42)") (class "Default")
      (node (ref "BBBLACK") (pin "42") (pinfunction "GPIO2_11_42") (pintype "passive"))
    )
    (net (code "73") (name "unconnected-(BBBLACK-GPIO2_12-Pad39)") (class "Default")
      (node (ref "BBBLACK") (pin "39") (pinfunction "GPIO2_12_39") (pintype "passive"))
    )
    (net (code "74") (name "unconnected-(BBBLACK-GPIO2_13-Pad40)") (class "Default")
      (node (ref "BBBLACK") (pin "40") (pinfunction "GPIO2_13_40") (pintype "passive"))
    )
    (net (code "75") (name "unconnected-(BBBLACK-GPIO2_22-Pad27)") (class "Default")
      (node (ref "BBBLACK") (pin "27") (pinfunction "GPIO2_22_27") (pintype "passive"))
    )
    (net (code "76") (name "unconnected-(BBBLACK-GPIO2_23-Pad29)") (class "Default")
      (node (ref "BBBLACK") (pin "29") (pinfunction "GPIO2_23_29") (pintype "passive"))
    )
    (net (code "77") (name "unconnected-(BBBLACK-GPIO2_24-Pad28)") (class "Default")
      (node (ref "BBBLACK") (pin "28") (pinfunction "GPIO2_24_28") (pintype "passive"))
    )
    (net (code "78") (name "unconnected-(BBBLACK-GPIO2_25-Pad30)") (class "Default")
      (node (ref "BBBLACK") (pin "30") (pinfunction "GPIO2_25_30") (pintype "passive"))
    )
    (net (code "79") (name "unconnected-(BBBLACK-GPIO3_19-Pad73)") (class "Default")
      (node (ref "BBBLACK") (pin "73") (pinfunction "GPIO3_19_73") (pintype "passive"))
    )
    (net (code "80") (name "unconnected-(BBBLACK-I2C1_SCL-Pad63)") (class "Default")
      (node (ref "BBBLACK") (pin "63") (pinfunction "I2C1_SCL_63") (pintype "passive"))
    )
    (net (code "81") (name "unconnected-(BBBLACK-I2C1_SDA-Pad64)") (class "Default")
      (node (ref "BBBLACK") (pin "64") (pinfunction "I2C1_SDA_64") (pintype "passive"))
    )
    (net (code "82") (name "unconnected-(BBBLACK-I2C2_SCL-Pad65)") (class "Default")
      (node (ref "BBBLACK") (pin "65") (pinfunction "I2C2_SCL_65") (pintype "passive"))
    )
    (net (code "83") (name "unconnected-(BBBLACK-I2C2_SDA-Pad66)") (class "Default")
      (node (ref "BBBLACK") (pin "66") (pinfunction "I2C2_SDA_66") (pintype "passive"))
    )
    (net (code "84") (name "unconnected-(BBBLACK-SPI1_CS0-Pad74)") (class "Default")
      (node (ref "BBBLACK") (pin "74") (pinfunction "SPI1_CS0_74") (pintype "passive"))
    )
    (net (code "85") (name "unconnected-(BBBLACK-SPI1_DI-Pad76)") (class "Default")
      (node (ref "BBBLACK") (pin "76") (pinfunction "SPI1_DI_76") (pintype "passive"))
    )
    (net (code "86") (name "unconnected-(BBBLACK-SPI1_DO-Pad75)") (class "Default")
      (node (ref "BBBLACK") (pin "75") (pinfunction "SPI1_DO_75") (pintype "passive"))
    )
    (net (code "87") (name "unconnected-(BBBLACK-SPI1_SCLK-Pad77)") (class "Default")
      (node (ref "BBBLACK") (pin "77") (pinfunction "SPI1_SCLK_77") (pintype "passive"))
    )
    (net (code "88") (name "unconnected-(BBBLACK-UART1_RXD-Pad72)") (class "Default")
      (node (ref "BBBLACK") (pin "72") (pinfunction "UART1_RXD_72") (pintype "passive"))
    )
    (net (code "89") (name "unconnected-(BBBLACK-UART1_TXD-Pad70)") (class "Default")
      (node (ref "BBBLACK") (pin "70") (pinfunction "UART1_TXD_70") (pintype "passive"))
    )
    (net (code "90") (name "unconnected-(BBBLACK-UART2_RXD-Pad68)") (class "Default")
      (node (ref "BBBLACK") (pin "68") (pinfunction "UART2_RXD_68") (pintype "passive"))
    )
    (net (code "91") (name "unconnected-(BBBLACK-UART2_TXD-Pad67)") (class "Default")
      (node (ref "BBBLACK") (pin "67") (pinfunction "UART2_TXD_67") (pintype "passive"))
    )
    (net (code "92") (name "unconnected-(BBBLACK-UART3_CTSN-Pad36)") (class "Default")
      (node (ref "BBBLACK") (pin "36") (pinfunction "UART3_CTSN_36") (pintype "passive"))
    )
    (net (code "93") (name "unconnected-(BBBLACK-UART3_RTSN-Pad34)") (class "Default")
      (node (ref "BBBLACK") (pin "34") (pinfunction "UART3_RTSN_34") (pintype "passive"))
    )
    (net (code "94") (name "unconnected-(BBBLACK-UART4_CTSN-Pad35)") (class "Default")
      (node (ref "BBBLACK") (pin "35") (pinfunction "UART4_CTSN_35") (pintype "passive"))
    )
    (net (code "95") (name "unconnected-(BBBLACK-UART4_RTSN-Pad33)") (class "Default")
      (node (ref "BBBLACK") (pin "33") (pinfunction "UART4_RTSN_33") (pintype "passive"))
    )
    (net (code "96") (name "unconnected-(BBBLACK-UART5_CTSN-Pad31)") (class "Default")
      (node (ref "BBBLACK") (pin "31") (pinfunction "UART5_CTSN_31") (pintype "passive"))
    )
    (net (code "97") (name "unconnected-(BBBLACK-UART5_RTSN-Pad32)") (class "Default")
      (node (ref "BBBLACK") (pin "32") (pinfunction "UART5_RTSN_32") (pintype "passive"))
    )
    (net (code "98") (name "unconnected-(BBBLACK-UART5_RXD-Pad38)") (class "Default")
      (node (ref "BBBLACK") (pin "38") (pinfunction "UART5_RXD_38") (pintype "passive"))
    )
    (net (code "99") (name "unconnected-(BBBLACK-UART5_TXD-Pad37)") (class "Default")
      (node (ref "BBBLACK") (pin "37") (pinfunction "UART5_TXD_37") (pintype "passive"))
    )
    (net (code "100") (name "unconnected-(BBBLACK-VDD_ADC-Pad78)") (class "Default")
      (node (ref "BBBLACK") (pin "78") (pinfunction "VDD_ADC_78") (pintype "passive"))
    )
  )
)
